# avrshift-uln2803.net
KiCad netlist of a schematic drawn in EAGLE
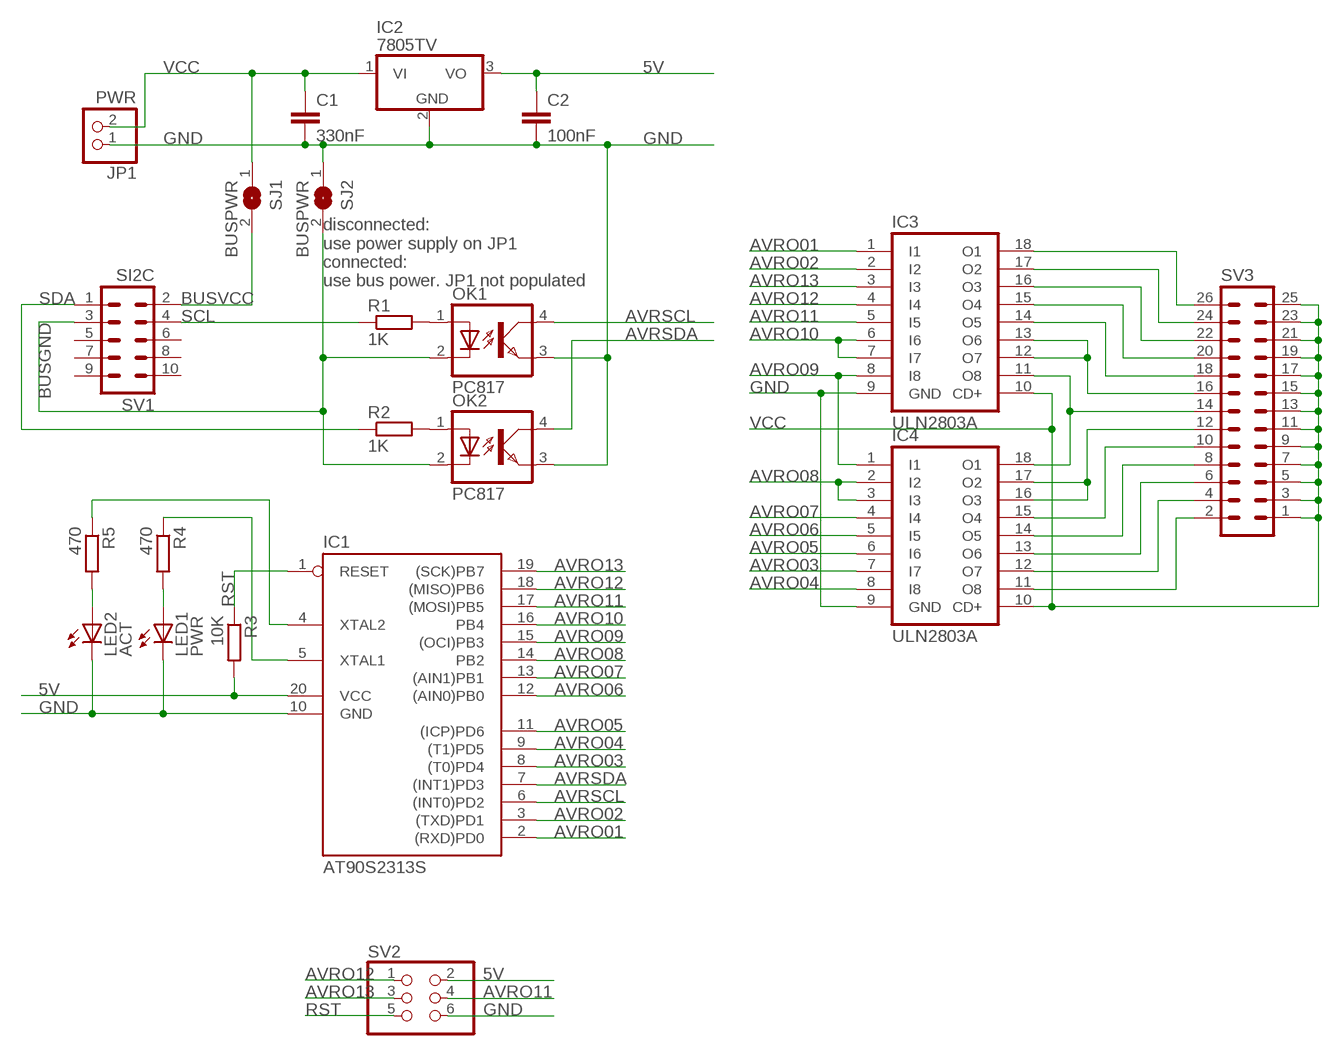
[diagram p0: schematic, sheet 1]

(export (version "E")
  (design (tool "Eeschema 10.0.6"))
  (components
    (comp (ref "C1")
      (value "330nF")
      (footprint "eagle-import:C2.5-3")
      (libsource (lib "eagle-import") (part "C2,5-3"))
    )
    (comp (ref "C2")
      (value "100nF")
      (footprint "eagle-import:C0805")
      (libsource (lib "eagle-import") (part "C-EUC0805"))
    )
    (comp (ref "IC1")
      (value "AT90S2313S")
      (footprint "eagle-import:SO20L")
      (libsource (lib "eagle-import") (part "AT90S2313S"))
    )
    (comp (ref "IC2")
      (value "7805TV")
      (footprint "eagle-import:TO220V")
      (libsource (lib "eagle-import") (part "78TV05"))
    )
    (comp (ref "IC3")
      (value "ULN2803A")
      (footprint "eagle-import:DIL18")
      (libsource (lib "eagle-import") (part "ULN2803A"))
    )
    (comp (ref "IC4")
      (value "ULN2803A")
      (footprint "eagle-import:DIL18")
      (libsource (lib "eagle-import") (part "ULN2803A"))
    )
    (comp (ref "JP1")
      (value "PWR")
      (footprint "eagle-import:1X02")
      (libsource (lib "eagle-import") (part "PINHD-1X2"))
    )
    (comp (ref "LED1")
      (value "PWR")
      (footprint "eagle-import:SML0805")
      (libsource (lib "eagle-import") (part "LEDSML0805"))
    )
    (comp (ref "LED2")
      (value "ACT")
      (footprint "eagle-import:SML0805")
      (libsource (lib "eagle-import") (part "LEDSML0805"))
    )
    (comp (ref "OK1")
      (value "PC817")
      (footprint "eagle-import:DIL04")
      (fields (field (name "MPN") "PC817X4J000F"))
      (libsource (lib "eagle-import") (part "PC817"))
    )
    (comp (ref "OK2")
      (value "PC817")
      (footprint "eagle-import:DIL04")
      (fields (field (name "MPN") "PC817X4J000F"))
      (libsource (lib "eagle-import") (part "PC817"))
    )
    (comp (ref "R1")
      (value "1K")
      (footprint "eagle-import:R0805")
      (libsource (lib "eagle-import") (part "R-EU_R0805"))
    )
    (comp (ref "R2")
      (value "1K")
      (footprint "eagle-import:R0805")
      (libsource (lib "eagle-import") (part "R-EU_R0805"))
    )
    (comp (ref "R3")
      (value "10K")
      (footprint "eagle-import:R0805")
      (libsource (lib "eagle-import") (part "R-EU_R0805"))
    )
    (comp (ref "R4")
      (value "470")
      (footprint "eagle-import:R0805")
      (libsource (lib "eagle-import") (part "R-EU_R0805"))
    )
    (comp (ref "R5")
      (value "470")
      (footprint "eagle-import:R0805")
      (libsource (lib "eagle-import") (part "R-EU_R0805"))
    )
    (comp (ref "SJ1")
      (value "BUSPWR")
      (footprint "eagle-import:SJ")
      (libsource (lib "eagle-import") (part "SJ"))
    )
    (comp (ref "SJ2")
      (value "BUSPWR")
      (footprint "eagle-import:SJ")
      (libsource (lib "eagle-import") (part "SJ"))
    )
    (comp (ref "SV1")
      (value "SI2C")
      (footprint "eagle-import:ML10")
      (libsource (lib "eagle-import") (part "ML10"))
    )
    (comp (ref "SV2")
      (value "PINHD-2X3")
      (footprint "eagle-import:2X03")
      (libsource (lib "eagle-import") (part "PINHD-2X3"))
    )
    (comp (ref "SV3")
      (value "ML26")
      (footprint "eagle-import:ML26")
      (libsource (lib "eagle-import") (part "ML26"))
    )
  )
  (nets
    (net (code "1") (name "/5V") (class "Default")
      (node (ref "C2") (pin "1") (pinfunction "1_1") (pintype "passive"))
      (node (ref "IC1") (pin "20") (pinfunction "VCC_20") (pintype "power_in"))
      (node (ref "IC2") (pin "3") (pinfunction "VO_3") (pintype "passive"))
      (node (ref "R3") (pin "2") (pinfunction "2_2") (pintype "passive"))
      (node (ref "SV2") (pin "2") (pinfunction "2_2") (pintype "passive"))
    )
    (net (code "2") (name "/AVRO01") (class "Default")
      (node (ref "IC1") (pin "2") (pinfunction "(RXD)PD0_2") (pintype "bidirectional"))
      (node (ref "IC3") (pin "1") (pinfunction "I1_1") (pintype "input"))
    )
    (net (code "3") (name "/AVRO02") (class "Default")
      (node (ref "IC1") (pin "3") (pinfunction "(TXD)PD1_3") (pintype "bidirectional"))
      (node (ref "IC3") (pin "2") (pinfunction "I2_2") (pintype "input"))
    )
    (net (code "4") (name "/AVRO03") (class "Default")
      (node (ref "IC1") (pin "8") (pinfunction "(T0)PD4_8") (pintype "bidirectional"))
      (node (ref "IC4") (pin "7") (pinfunction "I7_7") (pintype "input"))
    )
    (net (code "5") (name "/AVRO04") (class "Default")
      (node (ref "IC1") (pin "9") (pinfunction "(T1)PD5_9") (pintype "bidirectional"))
      (node (ref "IC4") (pin "8") (pinfunction "I8_8") (pintype "input"))
    )
    (net (code "6") (name "/AVRO05") (class "Default")
      (node (ref "IC1") (pin "11") (pinfunction "(ICP)PD6_11") (pintype "bidirectional"))
      (node (ref "IC4") (pin "6") (pinfunction "I6_6") (pintype "input"))
    )
    (net (code "7") (name "/AVRO06") (class "Default")
      (node (ref "IC1") (pin "12") (pinfunction "(AIN0)PB0_12") (pintype "bidirectional"))
      (node (ref "IC4") (pin "5") (pinfunction "I5_5") (pintype "input"))
    )
    (net (code "8") (name "/AVRO07") (class "Default")
      (node (ref "IC1") (pin "13") (pinfunction "(AIN1)PB1_13") (pintype "bidirectional"))
      (node (ref "IC4") (pin "4") (pinfunction "I4_4") (pintype "input"))
    )
    (net (code "9") (name "/AVRO08") (class "Default")
      (node (ref "IC1") (pin "14") (pinfunction "PB2_14") (pintype "bidirectional"))
      (node (ref "IC4") (pin "2") (pinfunction "I2_2") (pintype "input"))
      (node (ref "IC4") (pin "3") (pinfunction "I3_3") (pintype "input"))
    )
    (net (code "10") (name "/AVRO09") (class "Default")
      (node (ref "IC1") (pin "15") (pinfunction "(OCI)PB3_15") (pintype "bidirectional"))
      (node (ref "IC3") (pin "8") (pinfunction "I8_8") (pintype "input"))
      (node (ref "IC4") (pin "1") (pinfunction "I1_1") (pintype "input"))
    )
    (net (code "11") (name "/AVRO10") (class "Default")
      (node (ref "IC1") (pin "16") (pinfunction "PB4_16") (pintype "bidirectional"))
      (node (ref "IC3") (pin "6") (pinfunction "I6_6") (pintype "input"))
      (node (ref "IC3") (pin "7") (pinfunction "I7_7") (pintype "input"))
    )
    (net (code "12") (name "/AVRO11") (class "Default")
      (node (ref "IC1") (pin "17") (pinfunction "(MOSI)PB5_17") (pintype "bidirectional"))
      (node (ref "IC3") (pin "5") (pinfunction "I5_5") (pintype "input"))
      (node (ref "SV2") (pin "4") (pinfunction "4_4") (pintype "passive"))
    )
    (net (code "13") (name "/AVRO12") (class "Default")
      (node (ref "IC1") (pin "18") (pinfunction "(MISO)PB6_18") (pintype "bidirectional"))
      (node (ref "IC3") (pin "4") (pinfunction "I4_4") (pintype "input"))
      (node (ref "SV2") (pin "1") (pinfunction "1_1") (pintype "passive"))
    )
    (net (code "14") (name "/AVRO13") (class "Default")
      (node (ref "IC1") (pin "19") (pinfunction "(SCK)PB7_19") (pintype "bidirectional"))
      (node (ref "IC3") (pin "3") (pinfunction "I3_3") (pintype "input"))
      (node (ref "SV2") (pin "3") (pinfunction "3_3") (pintype "passive"))
    )
    (net (code "15") (name "/AVRSCL") (class "Default")
      (node (ref "IC1") (pin "6") (pinfunction "(INT0)PD2_6") (pintype "bidirectional"))
      (node (ref "OK1") (pin "4") (pinfunction "COL_4") (pintype "passive"))
    )
    (net (code "16") (name "/AVRSDA") (class "Default")
      (node (ref "IC1") (pin "7") (pinfunction "(INT1)PD3_7") (pintype "bidirectional"))
      (node (ref "OK2") (pin "4") (pinfunction "COL_4") (pintype "passive"))
    )
    (net (code "17") (name "/BUSGND") (class "Default")
      (node (ref "OK1") (pin "2") (pinfunction "C_2") (pintype "passive"))
      (node (ref "OK2") (pin "2") (pinfunction "C_2") (pintype "passive"))
      (node (ref "SJ2") (pin "2") (pinfunction "2_2") (pintype "passive"))
      (node (ref "SV1") (pin "3") (pinfunction "3_3") (pintype "passive"))
    )
    (net (code "18") (name "/BUSVCC") (class "Default")
      (node (ref "SJ1") (pin "2") (pinfunction "2_2") (pintype "passive"))
      (node (ref "SV1") (pin "2") (pinfunction "2_2") (pintype "passive"))
    )
    (net (code "19") (name "/GND") (class "Default")
      (node (ref "C1") (pin "2") (pinfunction "2_2") (pintype "passive"))
      (node (ref "C2") (pin "2") (pinfunction "2_2") (pintype "passive"))
      (node (ref "IC1") (pin "10") (pinfunction "GND_10") (pintype "power_in"))
      (node (ref "IC2") (pin "2") (pinfunction "GND_2") (pintype "passive"))
      (node (ref "IC3") (pin "9") (pinfunction "GND_9") (pintype "power_in"))
      (node (ref "IC4") (pin "9") (pinfunction "GND_9") (pintype "power_in"))
      (node (ref "JP1") (pin "1") (pinfunction "1_1") (pintype "passive"))
      (node (ref "LED1") (pin "C") (pinfunction "C_C") (pintype "passive"))
      (node (ref "LED2") (pin "C") (pinfunction "C_C") (pintype "passive"))
      (node (ref "OK1") (pin "3") (pinfunction "EMIT_3") (pintype "passive"))
      (node (ref "OK2") (pin "3") (pinfunction "EMIT_3") (pintype "passive"))
      (node (ref "SJ2") (pin "1") (pinfunction "1_1") (pintype "passive"))
      (node (ref "SV2") (pin "6") (pinfunction "6_6") (pintype "passive"))
    )
    (net (code "20") (name "/RST") (class "Default")
      (node (ref "IC1") (pin "1") (pinfunction "RESET_1") (pintype "bidirectional"))
      (node (ref "R3") (pin "1") (pinfunction "1_1") (pintype "passive"))
      (node (ref "SV2") (pin "5") (pinfunction "5_5") (pintype "passive"))
    )
    (net (code "21") (name "/SCL") (class "Default")
      (node (ref "R1") (pin "1") (pinfunction "1_1") (pintype "passive"))
      (node (ref "SV1") (pin "4") (pinfunction "4_4") (pintype "passive"))
    )
    (net (code "22") (name "/SDA") (class "Default")
      (node (ref "R2") (pin "1") (pinfunction "1_1") (pintype "passive"))
      (node (ref "SV1") (pin "1") (pinfunction "1_1") (pintype "passive"))
    )
    (net (code "23") (name "/VCC") (class "Default")
      (node (ref "C1") (pin "1") (pinfunction "1_1") (pintype "passive"))
      (node (ref "IC2") (pin "1") (pinfunction "VI_1") (pintype "input"))
      (node (ref "IC3") (pin "10") (pinfunction "CD+_10") (pintype "passive"))
      (node (ref "IC4") (pin "10") (pinfunction "CD+_10") (pintype "passive"))
      (node (ref "JP1") (pin "2") (pinfunction "2_2") (pintype "passive"))
      (node (ref "SJ1") (pin "1") (pinfunction "1_1") (pintype "passive"))
      (node (ref "SV3") (pin "1") (pinfunction "1_1") (pintype "passive"))
      (node (ref "SV3") (pin "11") (pinfunction "11_11") (pintype "passive"))
      (node (ref "SV3") (pin "13") (pinfunction "13_13") (pintype "passive"))
      (node (ref "SV3") (pin "15") (pinfunction "15_15") (pintype "passive"))
      (node (ref "SV3") (pin "17") (pinfunction "17_17") (pintype "passive"))
      (node (ref "SV3") (pin "19") (pinfunction "19_19") (pintype "passive"))
      (node (ref "SV3") (pin "21") (pinfunction "21_21") (pintype "passive"))
      (node (ref "SV3") (pin "23") (pinfunction "23_23") (pintype "passive"))
      (node (ref "SV3") (pin "25") (pinfunction "25_25") (pintype "passive"))
      (node (ref "SV3") (pin "3") (pinfunction "3_3") (pintype "passive"))
      (node (ref "SV3") (pin "5") (pinfunction "5_5") (pintype "passive"))
      (node (ref "SV3") (pin "7") (pinfunction "7_7") (pintype "passive"))
      (node (ref "SV3") (pin "9") (pinfunction "9_9") (pintype "passive"))
    )
    (net (code "24") (name "Net-(IC1-XTAL1)") (class "Default")
      (node (ref "IC1") (pin "5") (pinfunction "XTAL1_5") (pintype "bidirectional"))
      (node (ref "R4") (pin "1") (pinfunction "1_1") (pintype "passive"))
    )
    (net (code "25") (name "Net-(IC1-XTAL2)") (class "Default")
      (node (ref "IC1") (pin "4") (pinfunction "XTAL2_4") (pintype "bidirectional"))
      (node (ref "R5") (pin "1") (pinfunction "1_1") (pintype "passive"))
    )
    (net (code "26") (name "Net-(IC3-O1)") (class "Default")
      (node (ref "IC3") (pin "18") (pinfunction "O1_18") (pintype "open_collector"))
      (node (ref "SV3") (pin "26") (pinfunction "26_26") (pintype "passive"))
    )
    (net (code "27") (name "Net-(IC3-O2)") (class "Default")
      (node (ref "IC3") (pin "17") (pinfunction "O2_17") (pintype "open_collector"))
      (node (ref "SV3") (pin "24") (pinfunction "24_24") (pintype "passive"))
    )
    (net (code "28") (name "Net-(IC3-O3)") (class "Default")
      (node (ref "IC3") (pin "16") (pinfunction "O3_16") (pintype "open_collector"))
      (node (ref "SV3") (pin "22") (pinfunction "22_22") (pintype "passive"))
    )
    (net (code "29") (name "Net-(IC3-O4)") (class "Default")
      (node (ref "IC3") (pin "15") (pinfunction "O4_15") (pintype "open_collector"))
      (node (ref "SV3") (pin "20") (pinfunction "20_20") (pintype "passive"))
    )
    (net (code "30") (name "Net-(IC3-O5)") (class "Default")
      (node (ref "IC3") (pin "14") (pinfunction "O5_14") (pintype "open_collector"))
      (node (ref "SV3") (pin "18") (pinfunction "18_18") (pintype "passive"))
    )
    (net (code "31") (name "Net-(IC3-O6)") (class "Default")
      (node (ref "IC3") (pin "12") (pinfunction "O7_12") (pintype "open_collector"))
      (node (ref "IC3") (pin "13") (pinfunction "O6_13") (pintype "open_collector"))
      (node (ref "SV3") (pin "16") (pinfunction "16_16") (pintype "passive"))
    )
    (net (code "32") (name "Net-(IC3-O8)") (class "Default")
      (node (ref "IC3") (pin "11") (pinfunction "O8_11") (pintype "open_collector"))
      (node (ref "IC4") (pin "18") (pinfunction "O1_18") (pintype "open_collector"))
      (node (ref "SV3") (pin "14") (pinfunction "14_14") (pintype "passive"))
    )
    (net (code "33") (name "Net-(IC4-O2)") (class "Default")
      (node (ref "IC4") (pin "16") (pinfunction "O3_16") (pintype "open_collector"))
      (node (ref "IC4") (pin "17") (pinfunction "O2_17") (pintype "open_collector"))
      (node (ref "SV3") (pin "12") (pinfunction "12_12") (pintype "passive"))
    )
    (net (code "34") (name "Net-(IC4-O4)") (class "Default")
      (node (ref "IC4") (pin "15") (pinfunction "O4_15") (pintype "open_collector"))
      (node (ref "SV3") (pin "10") (pinfunction "10_10") (pintype "passive"))
    )
    (net (code "35") (name "Net-(IC4-O5)") (class "Default")
      (node (ref "IC4") (pin "14") (pinfunction "O5_14") (pintype "open_collector"))
      (node (ref "SV3") (pin "8") (pinfunction "8_8") (pintype "passive"))
    )
    (net (code "36") (name "Net-(IC4-O6)") (class "Default")
      (node (ref "IC4") (pin "13") (pinfunction "O6_13") (pintype "open_collector"))
      (node (ref "SV3") (pin "6") (pinfunction "6_6") (pintype "passive"))
    )
    (net (code "37") (name "Net-(IC4-O7)") (class "Default")
      (node (ref "IC4") (pin "12") (pinfunction "O7_12") (pintype "open_collector"))
      (node (ref "SV3") (pin "4") (pinfunction "4_4") (pintype "passive"))
    )
    (net (code "38") (name "Net-(IC4-O8)") (class "Default")
      (node (ref "IC4") (pin "11") (pinfunction "O8_11") (pintype "open_collector"))
      (node (ref "SV3") (pin "2") (pinfunction "2_2") (pintype "passive"))
    )
    (net (code "39") (name "Net-(LED1-PadA)") (class "Default")
      (node (ref "LED1") (pin "A") (pinfunction "A_A") (pintype "passive"))
      (node (ref "R4") (pin "2") (pinfunction "2_2") (pintype "passive"))
    )
    (net (code "40") (name "Net-(LED2-PadA)") (class "Default")
      (node (ref "LED2") (pin "A") (pinfunction "A_A") (pintype "passive"))
      (node (ref "R5") (pin "2") (pinfunction "2_2") (pintype "passive"))
    )
    (net (code "41") (name "Net-(OK1-A)") (class "Default")
      (node (ref "OK1") (pin "1") (pinfunction "A_1") (pintype "passive"))
      (node (ref "R1") (pin "2") (pinfunction "2_2") (pintype "passive"))
    )
    (net (code "42") (name "Net-(OK2-A)") (class "Default")
      (node (ref "OK2") (pin "1") (pinfunction "A_1") (pintype "passive"))
      (node (ref "R2") (pin "2") (pinfunction "2_2") (pintype "passive"))
    )
    (net (code "43") (name "unconnected-(SV1-Pad5)") (class "Default")
      (node (ref "SV1") (pin "5") (pinfunction "5_5") (pintype "passive"))
    )
    (net (code "44") (name "unconnected-(SV1-Pad6)") (class "Default")
      (node (ref "SV1") (pin "6") (pinfunction "6_6") (pintype "passive"))
    )
    (net (code "45") (name "unconnected-(SV1-Pad7)") (class "Default")
      (node (ref "SV1") (pin "7") (pinfunction "7_7") (pintype "passive"))
    )
    (net (code "46") (name "unconnected-(SV1-Pad8)") (class "Default")
      (node (ref "SV1") (pin "8") (pinfunction "8_8") (pintype "passive"))
    )
    (net (code "47") (name "unconnected-(SV1-Pad9)") (class "Default")
      (node (ref "SV1") (pin "9") (pinfunction "9_9") (pintype "passive"))
    )
    (net (code "48") (name "unconnected-(SV1-Pad10)") (class "Default")
      (node (ref "SV1") (pin "10") (pinfunction "10_10") (pintype "passive"))
    )
  )
)
